# Hatch2020Badge0805_1.net
KiCad netlist of a schematic drawn in EAGLE
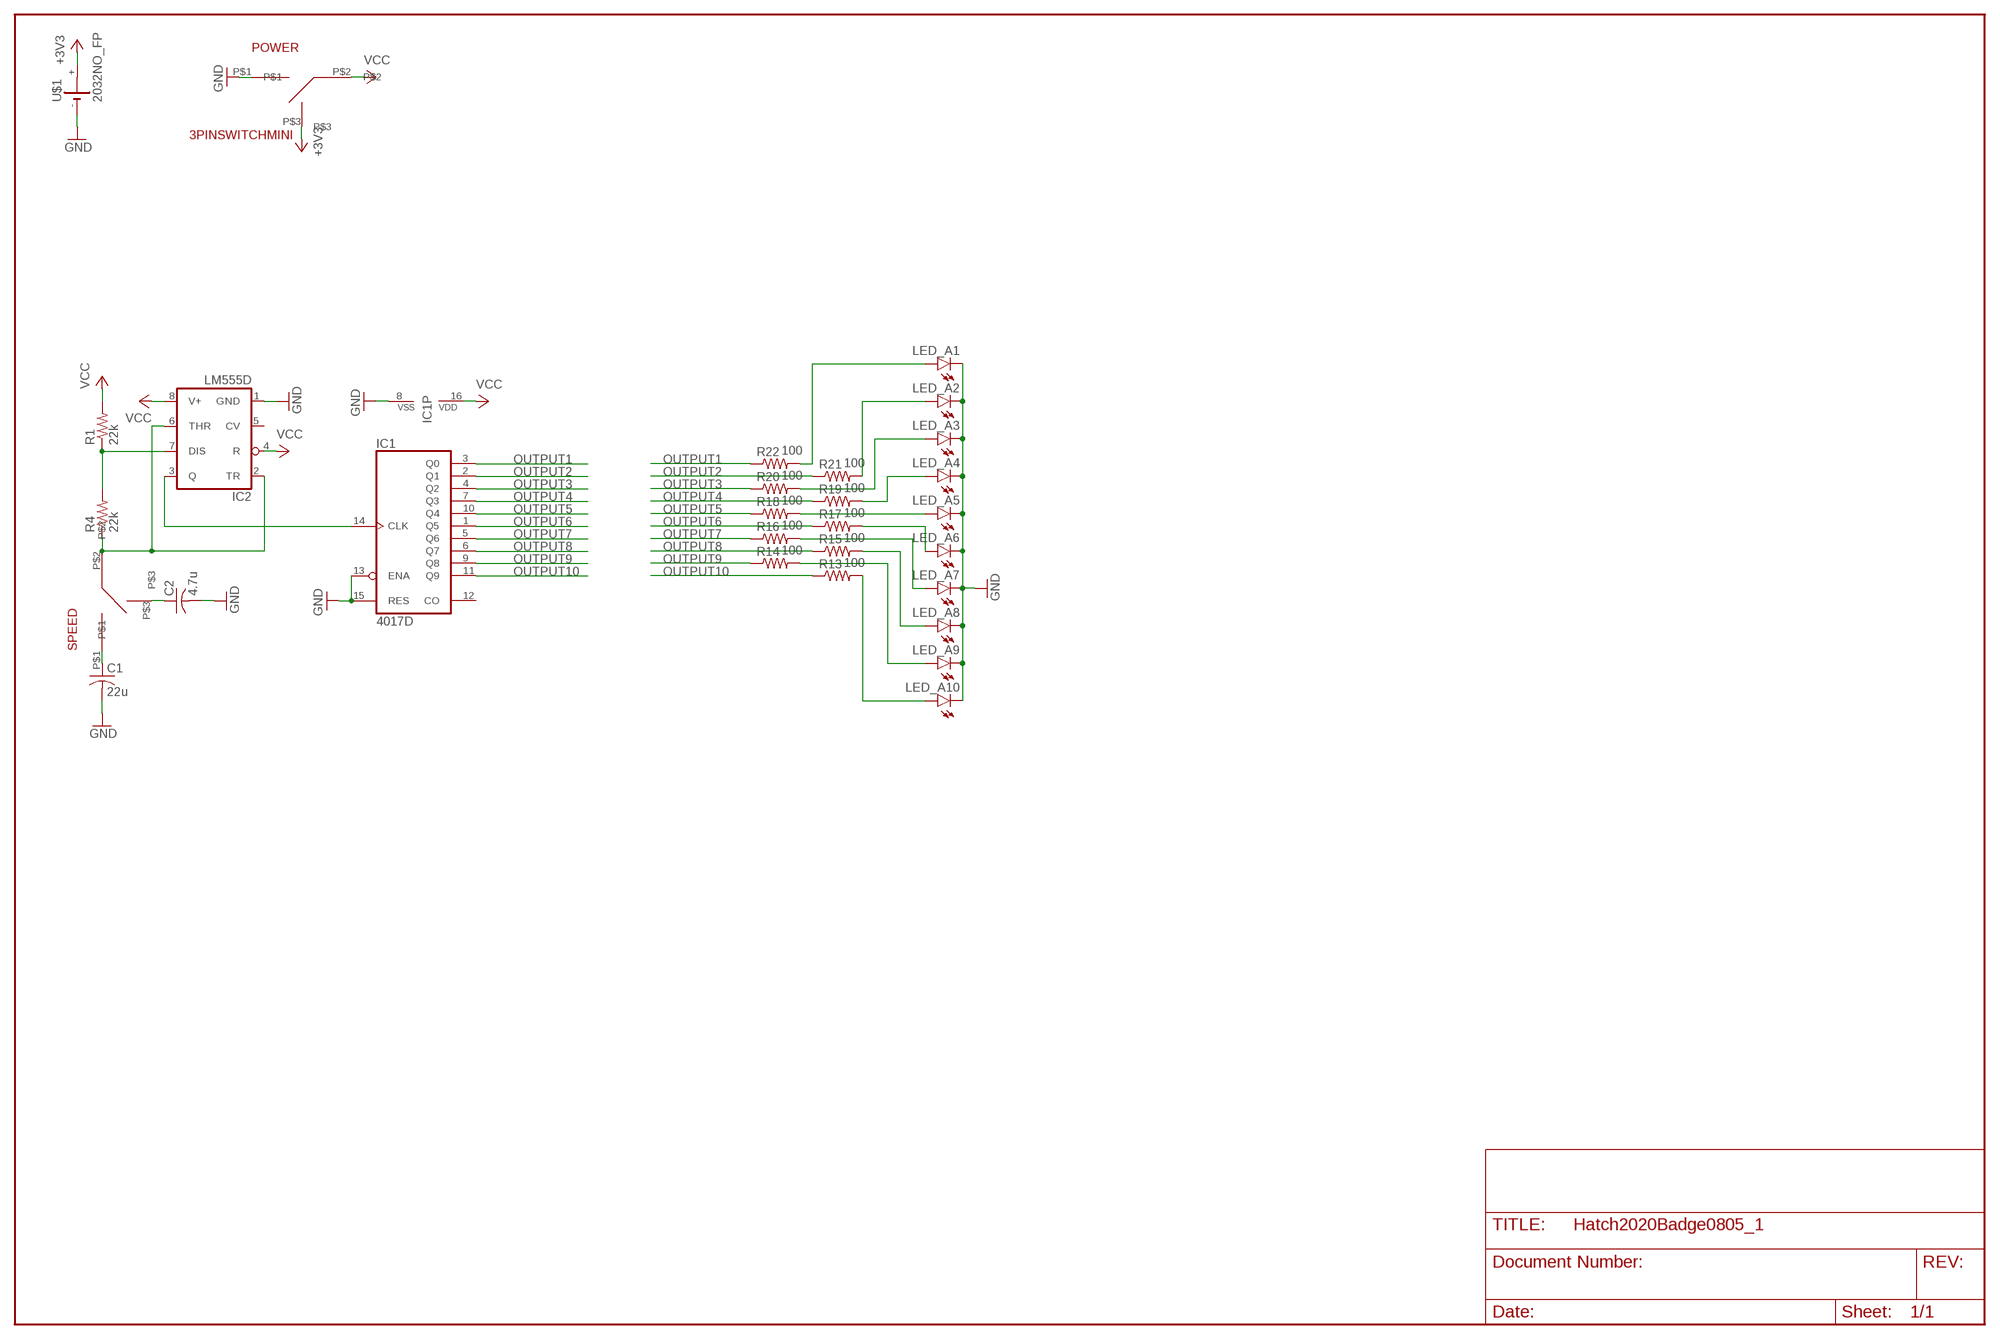
[diagram p0: schematic, sheet 1]

(export (version "E")
  (design (tool "Eeschema 10.0.6"))
  (components
    (comp (ref "C1")
      (value "22u")
      (footprint "eagle-import:C0805")
      (libsource (lib "eagle-import") (part "C-USC0805"))
    )
    (comp (ref "C2")
      (value "4.7u")
      (footprint "eagle-import:C0805")
      (libsource (lib "eagle-import") (part "C-USC0805"))
    )
    (comp (ref "IC1")
      (value "4017D")
      (footprint "eagle-import:SO16")
      (libsource (lib "eagle-import") (part "4017D"))
    )
    (comp (ref "IC2")
      (value "LM555D")
      (footprint "eagle-import:SO08")
      (libsource (lib "eagle-import") (part "555DLM"))
    )
    (comp (ref "LED_A1")
      (value "LEDSML0805")
      (footprint "eagle-import:SML0805")
      (libsource (lib "eagle-import") (part "LEDSML0805"))
    )
    (comp (ref "LED_A2")
      (value "LEDSML0805")
      (footprint "eagle-import:SML0805")
      (libsource (lib "eagle-import") (part "LEDSML0805"))
    )
    (comp (ref "LED_A3")
      (value "LEDSML0805")
      (footprint "eagle-import:SML0805")
      (libsource (lib "eagle-import") (part "LEDSML0805"))
    )
    (comp (ref "LED_A4")
      (value "LEDSML0805")
      (footprint "eagle-import:SML0805")
      (libsource (lib "eagle-import") (part "LEDSML0805"))
    )
    (comp (ref "LED_A5")
      (value "LEDSML0805")
      (footprint "eagle-import:SML0805")
      (libsource (lib "eagle-import") (part "LEDSML0805"))
    )
    (comp (ref "LED_A6")
      (value "LEDSML0805")
      (footprint "eagle-import:SML0805")
      (libsource (lib "eagle-import") (part "LEDSML0805"))
    )
    (comp (ref "LED_A7")
      (value "LEDSML0805")
      (footprint "eagle-import:SML0805")
      (libsource (lib "eagle-import") (part "LEDSML0805"))
    )
    (comp (ref "LED_A8")
      (value "LEDSML0805")
      (footprint "eagle-import:SML0805")
      (libsource (lib "eagle-import") (part "LEDSML0805"))
    )
    (comp (ref "LED_A9")
      (value "LEDSML0805")
      (footprint "eagle-import:SML0805")
      (libsource (lib "eagle-import") (part "LEDSML0805"))
    )
    (comp (ref "LED_A10")
      (value "LEDSML0805")
      (footprint "eagle-import:SML0805")
      (libsource (lib "eagle-import") (part "LEDSML0805"))
    )
    (comp (ref "POWER")
      (value "3PINSWITCHMINI")
      (footprint "eagle-import:3PINMINI")
      (libsource (lib "eagle-import") (part "3PINSWITCHMINI"))
    )
    (comp (ref "R1")
      (value "22k")
      (footprint "eagle-import:R0805")
      (libsource (lib "eagle-import") (part "R-US_R0805"))
    )
    (comp (ref "R4")
      (value "22k")
      (footprint "eagle-import:R0805")
      (libsource (lib "eagle-import") (part "R-US_R0805"))
    )
    (comp (ref "R13")
      (value "100")
      (footprint "eagle-import:R0805")
      (libsource (lib "eagle-import") (part "R-US_R0805"))
    )
    (comp (ref "R14")
      (value "100")
      (footprint "eagle-import:R0805")
      (libsource (lib "eagle-import") (part "R-US_R0805"))
    )
    (comp (ref "R15")
      (value "100")
      (footprint "eagle-import:R0805")
      (libsource (lib "eagle-import") (part "R-US_R0805"))
    )
    (comp (ref "R16")
      (value "100")
      (footprint "eagle-import:R0805")
      (libsource (lib "eagle-import") (part "R-US_R0805"))
    )
    (comp (ref "R17")
      (value "100")
      (footprint "eagle-import:R0805")
      (libsource (lib "eagle-import") (part "R-US_R0805"))
    )
    (comp (ref "R18")
      (value "100")
      (footprint "eagle-import:R0805")
      (libsource (lib "eagle-import") (part "R-US_R0805"))
    )
    (comp (ref "R19")
      (value "100")
      (footprint "eagle-import:R0805")
      (libsource (lib "eagle-import") (part "R-US_R0805"))
    )
    (comp (ref "R20")
      (value "100")
      (footprint "eagle-import:R0805")
      (libsource (lib "eagle-import") (part "R-US_R0805"))
    )
    (comp (ref "R21")
      (value "100")
      (footprint "eagle-import:R0805")
      (libsource (lib "eagle-import") (part "R-US_R0805"))
    )
    (comp (ref "R22")
      (value "100")
      (footprint "eagle-import:R0805")
      (libsource (lib "eagle-import") (part "R-US_R0805"))
    )
    (comp (ref "SPEED")
      (value "3PINSWITCHMINI")
      (footprint "eagle-import:3PINMINI")
      (libsource (lib "eagle-import") (part "3PINSWITCHMINI"))
    )
    (comp (ref "U$1")
      (value "2032NO_FP")
      (footprint "eagle-import:2032_NO_FP")
      (libsource (lib "eagle-import") (part "2032NO_FP"))
    )
  )
  (nets
    (net (code "1") (name "+3V3") (class "Default")
      (node (ref "POWER") (pin "P$3") (pinfunction "P$3_P$3") (pintype "bidirectional"))
      (node (ref "U$1") (pin "+") (pinfunction "+_+") (pintype "passive"))
    )
    (net (code "2") (name "/OUTPUT1") (class "Default")
      (node (ref "IC1") (pin "3") (pinfunction "Q0_3") (pintype "output"))
      (node (ref "R22") (pin "1") (pinfunction "1_1") (pintype "passive"))
    )
    (net (code "3") (name "/OUTPUT2") (class "Default")
      (node (ref "IC1") (pin "2") (pinfunction "Q1_2") (pintype "output"))
      (node (ref "R21") (pin "1") (pinfunction "1_1") (pintype "passive"))
    )
    (net (code "4") (name "/OUTPUT3") (class "Default")
      (node (ref "IC1") (pin "4") (pinfunction "Q2_4") (pintype "output"))
      (node (ref "R20") (pin "1") (pinfunction "1_1") (pintype "passive"))
    )
    (net (code "5") (name "/OUTPUT4") (class "Default")
      (node (ref "IC1") (pin "7") (pinfunction "Q3_7") (pintype "output"))
      (node (ref "R19") (pin "1") (pinfunction "1_1") (pintype "passive"))
    )
    (net (code "6") (name "/OUTPUT5") (class "Default")
      (node (ref "IC1") (pin "10") (pinfunction "Q4_10") (pintype "output"))
      (node (ref "R18") (pin "1") (pinfunction "1_1") (pintype "passive"))
    )
    (net (code "7") (name "/OUTPUT6") (class "Default")
      (node (ref "IC1") (pin "1") (pinfunction "Q5_1") (pintype "output"))
      (node (ref "R17") (pin "1") (pinfunction "1_1") (pintype "passive"))
    )
    (net (code "8") (name "/OUTPUT7") (class "Default")
      (node (ref "IC1") (pin "5") (pinfunction "Q6_5") (pintype "output"))
      (node (ref "R16") (pin "1") (pinfunction "1_1") (pintype "passive"))
    )
    (net (code "9") (name "/OUTPUT8") (class "Default")
      (node (ref "IC1") (pin "6") (pinfunction "Q7_6") (pintype "output"))
      (node (ref "R15") (pin "1") (pinfunction "1_1") (pintype "passive"))
    )
    (net (code "10") (name "/OUTPUT9") (class "Default")
      (node (ref "IC1") (pin "9") (pinfunction "Q8_9") (pintype "output"))
      (node (ref "R14") (pin "1") (pinfunction "1_1") (pintype "passive"))
    )
    (net (code "11") (name "/OUTPUT10") (class "Default")
      (node (ref "IC1") (pin "11") (pinfunction "Q9_11") (pintype "output"))
      (node (ref "R13") (pin "1") (pinfunction "1_1") (pintype "passive"))
    )
    (net (code "12") (name "GND") (class "Default")
      (node (ref "C1") (pin "2") (pinfunction "2_2") (pintype "passive"))
      (node (ref "C2") (pin "2") (pinfunction "2_2") (pintype "passive"))
      (node (ref "IC1") (pin "13") (pinfunction "ENA_13") (pintype "input"))
      (node (ref "IC1") (pin "15") (pinfunction "RES_15") (pintype "input"))
      (node (ref "IC1") (pin "8") (pinfunction "VSS_8") (pintype "power_in"))
      (node (ref "IC2") (pin "1") (pinfunction "GND_1") (pintype "power_in"))
      (node (ref "LED_A1") (pin "C") (pinfunction "C_C") (pintype "passive"))
      (node (ref "LED_A10") (pin "C") (pinfunction "C_C") (pintype "passive"))
      (node (ref "LED_A2") (pin "C") (pinfunction "C_C") (pintype "passive"))
      (node (ref "LED_A3") (pin "C") (pinfunction "C_C") (pintype "passive"))
      (node (ref "LED_A4") (pin "C") (pinfunction "C_C") (pintype "passive"))
      (node (ref "LED_A5") (pin "C") (pinfunction "C_C") (pintype "passive"))
      (node (ref "LED_A6") (pin "C") (pinfunction "C_C") (pintype "passive"))
      (node (ref "LED_A7") (pin "C") (pinfunction "C_C") (pintype "passive"))
      (node (ref "LED_A8") (pin "C") (pinfunction "C_C") (pintype "passive"))
      (node (ref "LED_A9") (pin "C") (pinfunction "C_C") (pintype "passive"))
      (node (ref "POWER") (pin "P$1") (pinfunction "P$1_P$1") (pintype "bidirectional"))
      (node (ref "U$1") (pin "-") (pinfunction "-_-") (pintype "passive"))
    )
    (net (code "13") (name "Net-(C1-Pad1)") (class "Default")
      (node (ref "C1") (pin "1") (pinfunction "1_1") (pintype "passive"))
      (node (ref "SPEED") (pin "P$1") (pinfunction "P$1_P$1") (pintype "bidirectional"))
    )
    (net (code "14") (name "Net-(C2-Pad1)") (class "Default")
      (node (ref "C2") (pin "1") (pinfunction "1_1") (pintype "passive"))
      (node (ref "SPEED") (pin "P$3") (pinfunction "P$3_P$3") (pintype "bidirectional"))
    )
    (net (code "15") (name "Net-(IC1A-CLK)") (class "Default")
      (node (ref "IC1") (pin "14") (pinfunction "CLK_14") (pintype "input"))
      (node (ref "IC2") (pin "3") (pinfunction "Q_3") (pintype "output"))
    )
    (net (code "16") (name "Net-(IC2-DIS)") (class "Default")
      (node (ref "IC2") (pin "7") (pinfunction "DIS_7") (pintype "input"))
      (node (ref "R1") (pin "1") (pinfunction "1_1") (pintype "passive"))
      (node (ref "R4") (pin "2") (pinfunction "2_2") (pintype "passive"))
    )
    (net (code "17") (name "Net-(IC2-THR)") (class "Default")
      (node (ref "IC2") (pin "2") (pinfunction "TR_2") (pintype "input"))
      (node (ref "IC2") (pin "6") (pinfunction "THR_6") (pintype "input"))
      (node (ref "R4") (pin "1") (pinfunction "1_1") (pintype "passive"))
      (node (ref "SPEED") (pin "P$2") (pinfunction "P$2_P$2") (pintype "bidirectional"))
    )
    (net (code "18") (name "Net-(LED_A1-PadA)") (class "Default")
      (node (ref "LED_A1") (pin "A") (pinfunction "A_A") (pintype "passive"))
      (node (ref "R22") (pin "2") (pinfunction "2_2") (pintype "passive"))
    )
    (net (code "19") (name "Net-(LED_A2-PadA)") (class "Default")
      (node (ref "LED_A2") (pin "A") (pinfunction "A_A") (pintype "passive"))
      (node (ref "R21") (pin "2") (pinfunction "2_2") (pintype "passive"))
    )
    (net (code "20") (name "Net-(LED_A3-PadA)") (class "Default")
      (node (ref "LED_A3") (pin "A") (pinfunction "A_A") (pintype "passive"))
      (node (ref "R20") (pin "2") (pinfunction "2_2") (pintype "passive"))
    )
    (net (code "21") (name "Net-(LED_A4-PadA)") (class "Default")
      (node (ref "LED_A4") (pin "A") (pinfunction "A_A") (pintype "passive"))
      (node (ref "R19") (pin "2") (pinfunction "2_2") (pintype "passive"))
    )
    (net (code "22") (name "Net-(LED_A5-PadA)") (class "Default")
      (node (ref "LED_A5") (pin "A") (pinfunction "A_A") (pintype "passive"))
      (node (ref "R18") (pin "2") (pinfunction "2_2") (pintype "passive"))
    )
    (net (code "23") (name "Net-(LED_A6-PadA)") (class "Default")
      (node (ref "LED_A6") (pin "A") (pinfunction "A_A") (pintype "passive"))
      (node (ref "R17") (pin "2") (pinfunction "2_2") (pintype "passive"))
    )
    (net (code "24") (name "Net-(LED_A7-PadA)") (class "Default")
      (node (ref "LED_A7") (pin "A") (pinfunction "A_A") (pintype "passive"))
      (node (ref "R16") (pin "2") (pinfunction "2_2") (pintype "passive"))
    )
    (net (code "25") (name "Net-(LED_A8-PadA)") (class "Default")
      (node (ref "LED_A8") (pin "A") (pinfunction "A_A") (pintype "passive"))
      (node (ref "R15") (pin "2") (pinfunction "2_2") (pintype "passive"))
    )
    (net (code "26") (name "Net-(LED_A9-PadA)") (class "Default")
      (node (ref "LED_A9") (pin "A") (pinfunction "A_A") (pintype "passive"))
      (node (ref "R14") (pin "2") (pinfunction "2_2") (pintype "passive"))
    )
    (net (code "27") (name "Net-(LED_A10-PadA)") (class "Default")
      (node (ref "LED_A10") (pin "A") (pinfunction "A_A") (pintype "passive"))
      (node (ref "R13") (pin "2") (pinfunction "2_2") (pintype "passive"))
    )
    (net (code "28") (name "VCC") (class "Default")
      (node (ref "IC1") (pin "16") (pinfunction "VDD_16") (pintype "power_in"))
      (node (ref "IC2") (pin "4") (pinfunction "R_4") (pintype "input"))
      (node (ref "IC2") (pin "8") (pinfunction "V+_8") (pintype "power_in"))
      (node (ref "POWER") (pin "P$2") (pinfunction "P$2_P$2") (pintype "bidirectional"))
      (node (ref "R1") (pin "2") (pinfunction "2_2") (pintype "passive"))
    )
    (net (code "29") (name "unconnected-(IC1A-CO-Pad12)") (class "Default")
      (node (ref "IC1") (pin "12") (pinfunction "CO_12") (pintype "output"))
    )
    (net (code "30") (name "unconnected-(IC2-CV-Pad5)") (class "Default")
      (node (ref "IC2") (pin "5") (pinfunction "CV_5") (pintype "input"))
    )
  )
)
